# BadUSB-W.net
KiCad netlist of a schematic drawn in EAGLE
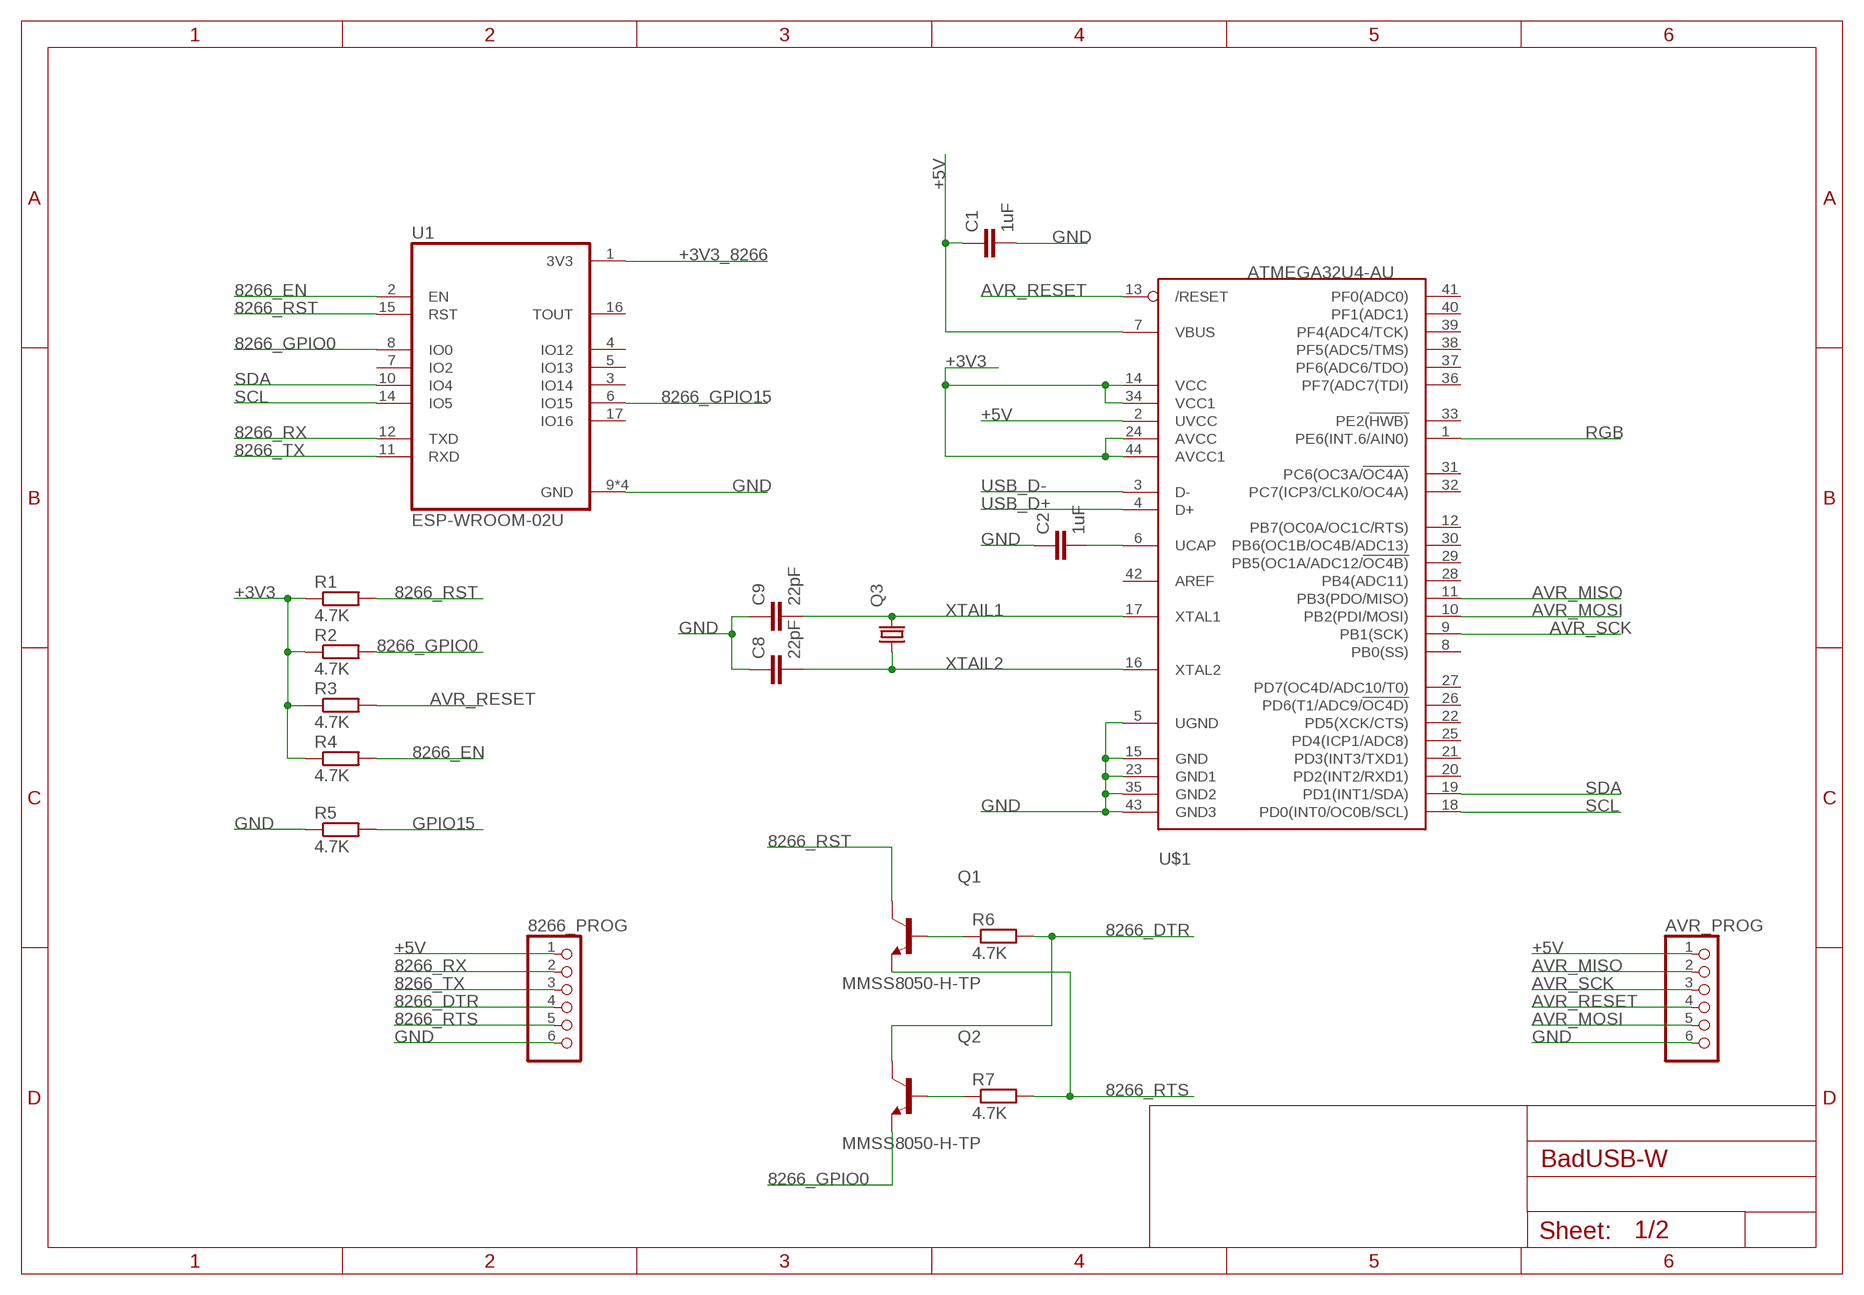
[diagram p0: schematic, sheet 1]
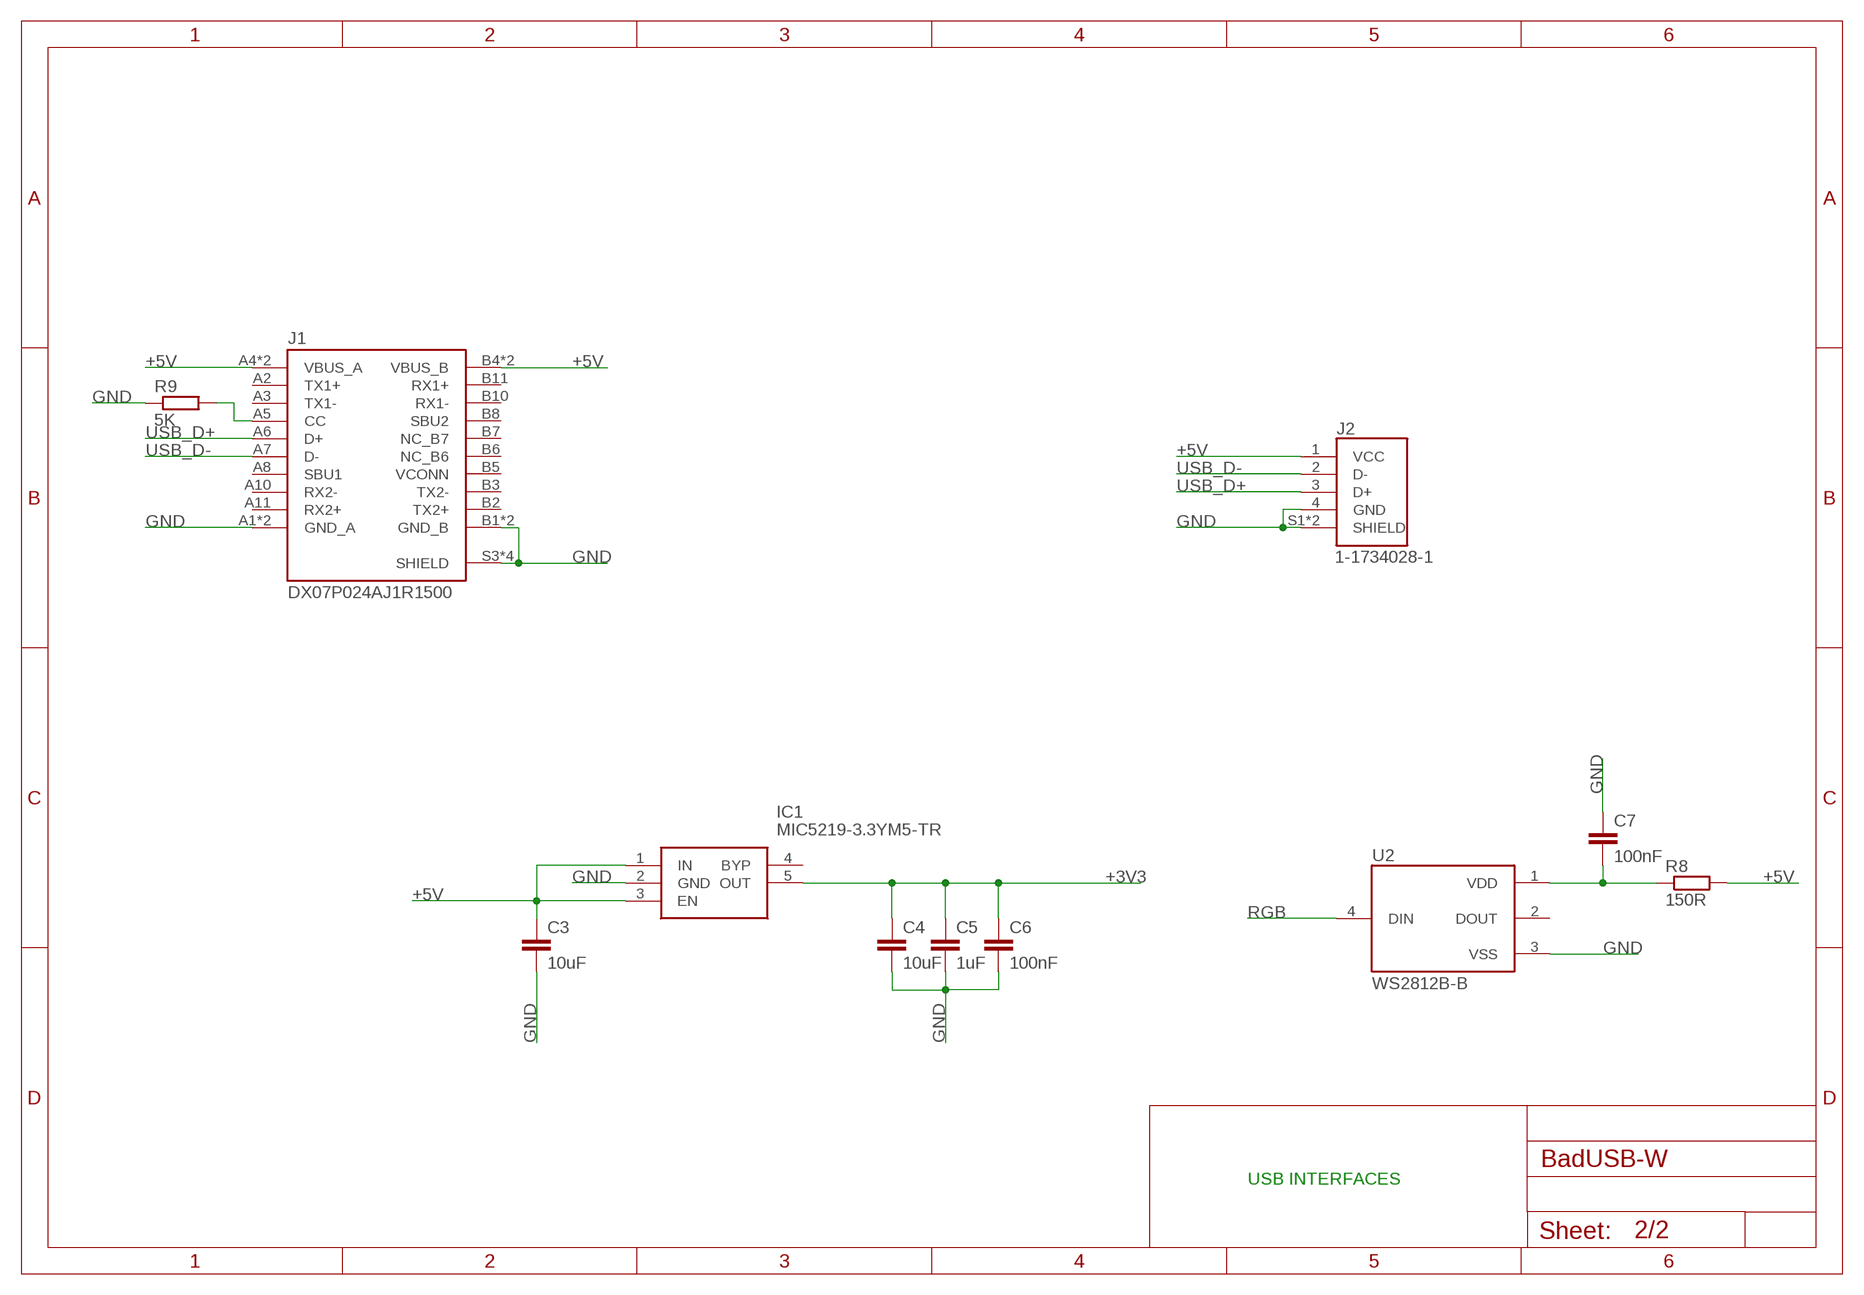
[diagram p1: schematic, sheet 2]

(export (version "E")
  (design (tool "Eeschema 10.0.6"))
  (components
    (comp (ref "C3")
      (value "10uF")
      (footprint "eagle-import:C0603K")
      (libsource (lib "eagle-import") (part "C-EUC0603K"))
    )
    (comp (ref "C4")
      (value "10uF")
      (footprint "eagle-import:C0603K")
      (libsource (lib "eagle-import") (part "C-EUC0603K"))
    )
    (comp (ref "C5")
      (value "1uF")
      (footprint "eagle-import:C0603K")
      (libsource (lib "eagle-import") (part "C-EUC0603K"))
    )
    (comp (ref "C6")
      (value "100nF")
      (footprint "eagle-import:C0603K")
      (libsource (lib "eagle-import") (part "C-EUC0603K"))
    )
    (comp (ref "C7")
      (value "100nF")
      (footprint "eagle-import:C0603K")
      (libsource (lib "eagle-import") (part "C-EUC0603K"))
    )
    (comp (ref "IC1")
      (value "MIC5219-3.3YM5-TR")
      (footprint "eagle-import:SOT95P280X130-5N")
      (fields (field (name "MOUSER_PART_NUMBER") "998-MIC5219-3.3YM5TR"))
      (libsource (lib "eagle-import") (part "MIC5219-3.3YM5-TR"))
    )
    (comp (ref "J1")
      (value "DX07P024AJ1R1500")
      (footprint "eagle-import:JAE_DX07P024AJ1R1500")
      (fields (field (name "MF") "JAE Electronics"))
      (libsource (lib "eagle-import") (part "DX07P024AJ1R1500"))
    )
    (comp (ref "J2")
      (value "1-1734028-1")
      (footprint "eagle-import:TE_1-1734028-1")
      (fields (field (name "MF") "TE Connectivity"))
      (libsource (lib "eagle-import") (part "1-1734028-1"))
    )
    (comp (ref "R8")
      (value "150R")
      (footprint "eagle-import:R0603")
      (libsource (lib "eagle-import") (part "R-EU_R0603"))
    )
    (comp (ref "R9")
      (value "5K")
      (footprint "eagle-import:R0603")
      (libsource (lib "eagle-import") (part "R-EU_R0603"))
    )
    (comp (ref "U2")
      (value "WS2812B-B")
      (footprint "eagle-import:LED_WS2812B-B")
      (fields (field (name "MF") "Worldsemi"))
      (libsource (lib "eagle-import") (part "WS2812B-B"))
    )
    (comp (ref "8266_PROG")
      (value "PINHD-1X6")
      (footprint "eagle-import:1X06")
      (libsource (lib "eagle-import") (part "PINHD-1X6"))
    )
    (comp (ref "AVR_PROG")
      (value "PINHD-1X6")
      (footprint "eagle-import:1X06")
      (libsource (lib "eagle-import") (part "PINHD-1X6"))
    )
    (comp (ref "C1")
      (value "1uF")
      (footprint "eagle-import:C0603K")
      (libsource (lib "eagle-import") (part "C-EUC0603K"))
    )
    (comp (ref "C2")
      (value "1uF")
      (footprint "eagle-import:C0603K")
      (libsource (lib "eagle-import") (part "C-EUC0603K"))
    )
    (comp (ref "C8")
      (value "22pF")
      (footprint "eagle-import:C0603K")
      (libsource (lib "eagle-import") (part "C-EUC0603K"))
    )
    (comp (ref "C9")
      (value "22pF")
      (footprint "eagle-import:C0603K")
      (libsource (lib "eagle-import") (part "C-EUC0603K"))
    )
    (comp (ref "Q1")
      (value "MMSS8050-H-TP")
      (footprint "eagle-import:TRANS_MMSS8050-H-TP")
      (fields (field (name "MF") "Micro Commercial"))
      (libsource (lib "eagle-import") (part "MMSS8050-H-TP"))
    )
    (comp (ref "Q2")
      (value "MMSS8050-H-TP")
      (footprint "eagle-import:TRANS_MMSS8050-H-TP")
      (fields (field (name "MF") "Micro Commercial"))
      (libsource (lib "eagle-import") (part "MMSS8050-H-TP"))
    )
    (comp (ref "Q3")
      (value "KX-7")
      (footprint "eagle-import:3.2X2.5_KX-7")
      (libsource (lib "eagle-import") (part "KX-7"))
    )
    (comp (ref "R1")
      (value "4.7K")
      (footprint "eagle-import:R0603")
      (libsource (lib "eagle-import") (part "R-EU_R0603"))
    )
    (comp (ref "R2")
      (value "4.7K")
      (footprint "eagle-import:R0603")
      (libsource (lib "eagle-import") (part "R-EU_R0603"))
    )
    (comp (ref "R3")
      (value "4.7K")
      (footprint "eagle-import:R0603")
      (libsource (lib "eagle-import") (part "R-EU_R0603"))
    )
    (comp (ref "R4")
      (value "4.7K")
      (footprint "eagle-import:R0603")
      (libsource (lib "eagle-import") (part "R-EU_R0603"))
    )
    (comp (ref "R5")
      (value "4.7K")
      (footprint "eagle-import:R0603")
      (libsource (lib "eagle-import") (part "R-EU_R0603"))
    )
    (comp (ref "R6")
      (value "4.7K")
      (footprint "eagle-import:R0603")
      (libsource (lib "eagle-import") (part "R-EU_R0603"))
    )
    (comp (ref "R7")
      (value "4.7K")
      (footprint "eagle-import:R0603")
      (libsource (lib "eagle-import") (part "R-EU_R0603"))
    )
    (comp (ref "U$1")
      (value "ATMEGA32U4-AU")
      (footprint "eagle-import:TQFP44")
      (libsource (lib "eagle-import") (part "ATMEGA32U4-AU"))
    )
    (comp (ref "U1")
      (value "ESP-WROOM-02U")
      (footprint "eagle-import:MODULE_ESP-WROOM-02U")
      (fields (field (name "MF") "Espressif Systems"))
      (libsource (lib "eagle-import") (part "ESP-WROOM-02U"))
    )
  )
  (nets
    (net (code "1") (name "+3V3") (class "Default")
      (node (ref "C4") (pin "1") (pinfunction "1_1") (pintype "passive"))
      (node (ref "C5") (pin "1") (pinfunction "1_1") (pintype "passive"))
      (node (ref "C6") (pin "1") (pinfunction "1_1") (pintype "passive"))
      (node (ref "IC1") (pin "5") (pinfunction "OUT_5") (pintype "bidirectional"))
      (node (ref "R1") (pin "1") (pinfunction "1_1") (pintype "passive"))
      (node (ref "R2") (pin "1") (pinfunction "1_1") (pintype "passive"))
      (node (ref "R3") (pin "1") (pinfunction "1_1") (pintype "passive"))
      (node (ref "R4") (pin "1") (pinfunction "1_1") (pintype "passive"))
      (node (ref "U$1") (pin "14") (pinfunction "VCC_14") (pintype "bidirectional"))
      (node (ref "U$1") (pin "24") (pinfunction "AVCC_24") (pintype "bidirectional"))
      (node (ref "U$1") (pin "34") (pinfunction "VCC1_34") (pintype "bidirectional"))
      (node (ref "U$1") (pin "44") (pinfunction "AVCC1_44") (pintype "bidirectional"))
    )
    (net (code "2") (name "+3V3_8266") (class "Default")
      (node (ref "U1") (pin "1") (pinfunction "3V3_1") (pintype "power_in"))
    )
    (net (code "3") (name "+5V") (class "Default")
      (node (ref "8266_PROG") (pin "1") (pinfunction "1_1") (pintype "passive"))
      (node (ref "AVR_PROG") (pin "1") (pinfunction "1_1") (pintype "passive"))
      (node (ref "C1") (pin "1") (pinfunction "1_1") (pintype "passive"))
      (node (ref "C3") (pin "1") (pinfunction "1_1") (pintype "passive"))
      (node (ref "IC1") (pin "1") (pinfunction "IN_1") (pintype "bidirectional"))
      (node (ref "IC1") (pin "3") (pinfunction "EN_3") (pintype "bidirectional"))
      (node (ref "J1") (pin "A4") (pinfunction "VBUS_A_A4") (pintype "power_in"))
      (node (ref "J1") (pin "A9") (pinfunction "VBUS_A_A9") (pintype "power_in"))
      (node (ref "J1") (pin "B4") (pinfunction "VBUS_B_B4") (pintype "power_in"))
      (node (ref "J1") (pin "B9") (pinfunction "VBUS_B_B9") (pintype "power_in"))
      (node (ref "J2") (pin "1") (pinfunction "VCC_1") (pintype "power_in"))
      (node (ref "R8") (pin "2") (pinfunction "2_2") (pintype "passive"))
      (node (ref "U$1") (pin "2") (pinfunction "UVCC_2") (pintype "bidirectional"))
      (node (ref "U$1") (pin "7") (pinfunction "VBUS_7") (pintype "bidirectional"))
    )
    (net (code "4") (name "8266_DTR") (class "Default")
      (node (ref "8266_PROG") (pin "4") (pinfunction "4_4") (pintype "passive"))
      (node (ref "Q2") (pin "3") (pinfunction "C_3") (pintype "passive"))
      (node (ref "R6") (pin "2") (pinfunction "2_2") (pintype "passive"))
    )
    (net (code "5") (name "8266_EN") (class "Default")
      (node (ref "R4") (pin "2") (pinfunction "2_2") (pintype "passive"))
      (node (ref "U1") (pin "2") (pinfunction "EN_2") (pintype "input"))
    )
    (net (code "6") (name "8266_GPIO0") (class "Default")
      (node (ref "Q2") (pin "2") (pinfunction "E_2") (pintype "passive"))
      (node (ref "R2") (pin "2") (pinfunction "2_2") (pintype "passive"))
      (node (ref "U1") (pin "8") (pinfunction "IO0_8") (pintype "bidirectional"))
    )
    (net (code "7") (name "8266_GPIO15") (class "Default")
      (node (ref "U1") (pin "6") (pinfunction "IO15_6") (pintype "bidirectional"))
    )
    (net (code "8") (name "8266_RST") (class "Default")
      (node (ref "Q1") (pin "3") (pinfunction "C_3") (pintype "passive"))
      (node (ref "R1") (pin "2") (pinfunction "2_2") (pintype "passive"))
      (node (ref "U1") (pin "15") (pinfunction "RST_15") (pintype "input"))
    )
    (net (code "9") (name "8266_RTS") (class "Default")
      (node (ref "8266_PROG") (pin "5") (pinfunction "5_5") (pintype "passive"))
      (node (ref "Q1") (pin "2") (pinfunction "E_2") (pintype "passive"))
      (node (ref "R7") (pin "2") (pinfunction "2_2") (pintype "passive"))
    )
    (net (code "10") (name "8266_RX") (class "Default")
      (node (ref "8266_PROG") (pin "2") (pinfunction "2_2") (pintype "passive"))
      (node (ref "U1") (pin "12") (pinfunction "TXD_12") (pintype "bidirectional"))
    )
    (net (code "11") (name "8266_TX") (class "Default")
      (node (ref "8266_PROG") (pin "3") (pinfunction "3_3") (pintype "passive"))
      (node (ref "U1") (pin "11") (pinfunction "RXD_11") (pintype "bidirectional"))
    )
    (net (code "12") (name "AVR_MISO") (class "Default")
      (node (ref "AVR_PROG") (pin "2") (pinfunction "2_2") (pintype "passive"))
      (node (ref "U$1") (pin "11") (pinfunction "PB3(PDO/MISO)_11") (pintype "bidirectional"))
    )
    (net (code "13") (name "AVR_MOSI") (class "Default")
      (node (ref "AVR_PROG") (pin "5") (pinfunction "5_5") (pintype "passive"))
      (node (ref "U$1") (pin "10") (pinfunction "PB2(PDI/MOSI)_10") (pintype "bidirectional"))
    )
    (net (code "14") (name "AVR_RESET") (class "Default")
      (node (ref "AVR_PROG") (pin "4") (pinfunction "4_4") (pintype "passive"))
      (node (ref "R3") (pin "2") (pinfunction "2_2") (pintype "passive"))
      (node (ref "U$1") (pin "13") (pinfunction "/RESET_13") (pintype "bidirectional"))
    )
    (net (code "15") (name "AVR_SCK") (class "Default")
      (node (ref "AVR_PROG") (pin "3") (pinfunction "3_3") (pintype "passive"))
      (node (ref "U$1") (pin "9") (pinfunction "PB1(SCK)_9") (pintype "bidirectional"))
    )
    (net (code "16") (name "GND") (class "Default")
      (node (ref "8266_PROG") (pin "6") (pinfunction "6_6") (pintype "passive"))
      (node (ref "AVR_PROG") (pin "6") (pinfunction "6_6") (pintype "passive"))
      (node (ref "C1") (pin "2") (pinfunction "2_2") (pintype "passive"))
      (node (ref "C2") (pin "1") (pinfunction "1_1") (pintype "passive"))
      (node (ref "C3") (pin "2") (pinfunction "2_2") (pintype "passive"))
      (node (ref "C4") (pin "2") (pinfunction "2_2") (pintype "passive"))
      (node (ref "C5") (pin "2") (pinfunction "2_2") (pintype "passive"))
      (node (ref "C6") (pin "2") (pinfunction "2_2") (pintype "passive"))
      (node (ref "C7") (pin "1") (pinfunction "1_1") (pintype "passive"))
      (node (ref "C8") (pin "1") (pinfunction "1_1") (pintype "passive"))
      (node (ref "C9") (pin "1") (pinfunction "1_1") (pintype "passive"))
      (node (ref "IC1") (pin "2") (pinfunction "GND_2") (pintype "bidirectional"))
      (node (ref "J1") (pin "A1") (pinfunction "GND_A_A1") (pintype "power_in"))
      (node (ref "J1") (pin "A12") (pinfunction "GND_A_A12") (pintype "power_in"))
      (node (ref "J1") (pin "B1") (pinfunction "GND_B_B1") (pintype "power_in"))
      (node (ref "J1") (pin "B12") (pinfunction "GND_B_B12") (pintype "power_in"))
      (node (ref "J1") (pin "S3") (pinfunction "SHIELD_S3") (pintype "passive"))
      (node (ref "J1") (pin "S4") (pinfunction "SHIELD_S4") (pintype "passive"))
      (node (ref "J1") (pin "S5") (pinfunction "SHIELD_S5") (pintype "passive"))
      (node (ref "J1") (pin "S6") (pinfunction "SHIELD_S6") (pintype "passive"))
      (node (ref "J2") (pin "4") (pinfunction "GND_4") (pintype "power_in"))
      (node (ref "J2") (pin "S1") (pinfunction "SHIELD_S1") (pintype "power_in"))
      (node (ref "J2") (pin "S2") (pinfunction "SHIELD_S2") (pintype "power_in"))
      (node (ref "R5") (pin "1") (pinfunction "1_1") (pintype "passive"))
      (node (ref "R9") (pin "1") (pinfunction "1_1") (pintype "passive"))
      (node (ref "U$1") (pin "15") (pinfunction "GND_15") (pintype "bidirectional"))
      (node (ref "U$1") (pin "23") (pinfunction "GND1_23") (pintype "bidirectional"))
      (node (ref "U$1") (pin "35") (pinfunction "GND2_35") (pintype "bidirectional"))
      (node (ref "U$1") (pin "43") (pinfunction "GND3_43") (pintype "bidirectional"))
      (node (ref "U$1") (pin "5") (pinfunction "UGND_5") (pintype "bidirectional"))
      (node (ref "U1") (pin "13") (pinfunction "GND_13") (pintype "power_in"))
      (node (ref "U1") (pin "18") (pinfunction "GND_18") (pintype "power_in"))
      (node (ref "U1") (pin "19") (pinfunction "GND_19") (pintype "power_in"))
      (node (ref "U1") (pin "9") (pinfunction "GND_9") (pintype "power_in"))
      (node (ref "U2") (pin "3") (pinfunction "VSS_3") (pintype "power_in"))
    )
    (net (code "17") (name "GPIO15") (class "Default")
      (node (ref "R5") (pin "2") (pinfunction "2_2") (pintype "passive"))
    )
    (net (code "18") (name "Net-(J1-CC)") (class "Default")
      (node (ref "J1") (pin "A5") (pinfunction "CC_A5") (pintype "bidirectional"))
      (node (ref "R9") (pin "2") (pinfunction "2_2") (pintype "passive"))
    )
    (net (code "19") (name "Net-(Q1-B)") (class "Default")
      (node (ref "Q1") (pin "1") (pinfunction "B_1") (pintype "passive"))
      (node (ref "R6") (pin "1") (pinfunction "1_1") (pintype "passive"))
    )
    (net (code "20") (name "Net-(Q2-B)") (class "Default")
      (node (ref "Q2") (pin "1") (pinfunction "B_1") (pintype "passive"))
      (node (ref "R7") (pin "1") (pinfunction "1_1") (pintype "passive"))
    )
    (net (code "21") (name "Net-(U$1-UCAP)") (class "Default")
      (node (ref "C2") (pin "2") (pinfunction "2_2") (pintype "passive"))
      (node (ref "U$1") (pin "6") (pinfunction "UCAP_6") (pintype "bidirectional"))
    )
    (net (code "22") (name "Net-(U2-VDD)") (class "Default")
      (node (ref "C7") (pin "2") (pinfunction "2_2") (pintype "passive"))
      (node (ref "R8") (pin "1") (pinfunction "1_1") (pintype "passive"))
      (node (ref "U2") (pin "1") (pinfunction "VDD_1") (pintype "power_in"))
    )
    (net (code "23") (name "RGB") (class "Default")
      (node (ref "U$1") (pin "1") (pinfunction "PE6(INT.6/AIN0)_1") (pintype "bidirectional"))
      (node (ref "U2") (pin "4") (pinfunction "DIN_4") (pintype "input"))
    )
    (net (code "24") (name "SCL") (class "Default")
      (node (ref "U$1") (pin "18") (pinfunction "PD0(INT0/OC0B/SCL)_18") (pintype "bidirectional"))
      (node (ref "U1") (pin "14") (pinfunction "IO5_14") (pintype "bidirectional"))
    )
    (net (code "25") (name "SDA") (class "Default")
      (node (ref "U$1") (pin "19") (pinfunction "PD1(INT1/SDA)_19") (pintype "bidirectional"))
      (node (ref "U1") (pin "10") (pinfunction "IO4_10") (pintype "bidirectional"))
    )
    (net (code "26") (name "USB_D+") (class "Default")
      (node (ref "J1") (pin "A6") (pinfunction "D+_A6") (pintype "bidirectional"))
      (node (ref "J2") (pin "3") (pinfunction "D+_3") (pintype "bidirectional"))
      (node (ref "U$1") (pin "4") (pinfunction "D+_4") (pintype "bidirectional"))
    )
    (net (code "27") (name "USB_D-") (class "Default")
      (node (ref "J1") (pin "A7") (pinfunction "D-_A7") (pintype "bidirectional"))
      (node (ref "J2") (pin "2") (pinfunction "D-_2") (pintype "bidirectional"))
      (node (ref "U$1") (pin "3") (pinfunction "D-_3") (pintype "bidirectional"))
    )
    (net (code "28") (name "XTAIL1") (class "Default")
      (node (ref "C9") (pin "2") (pinfunction "2_2") (pintype "passive"))
      (node (ref "Q3") (pin "3") (pinfunction "2_3") (pintype "passive"))
      (node (ref "U$1") (pin "17") (pinfunction "XTAL1_17") (pintype "bidirectional"))
    )
    (net (code "29") (name "XTAIL2") (class "Default")
      (node (ref "C8") (pin "2") (pinfunction "2_2") (pintype "passive"))
      (node (ref "Q3") (pin "1") (pinfunction "1_1") (pintype "passive"))
      (node (ref "U$1") (pin "16") (pinfunction "XTAL2_16") (pintype "bidirectional"))
    )
    (net (code "30") (name "unconnected-(IC1-BYP-Pad4)") (class "Default")
      (node (ref "IC1") (pin "4") (pinfunction "BYP_4") (pintype "bidirectional"))
    )
    (net (code "31") (name "unconnected-(J1-NC_B6-PadB6)") (class "Default")
      (node (ref "J1") (pin "B6") (pinfunction "NC_B6_B6") (pintype "no_connect"))
    )
    (net (code "32") (name "unconnected-(J1-NC_B7-PadB7)") (class "Default")
      (node (ref "J1") (pin "B7") (pinfunction "NC_B7_B7") (pintype "no_connect"))
    )
    (net (code "33") (name "unconnected-(J1-RX1+-PadB11)") (class "Default")
      (node (ref "J1") (pin "B11") (pinfunction "RX1+_B11") (pintype "bidirectional"))
    )
    (net (code "34") (name "unconnected-(J1-RX1--PadB10)") (class "Default")
      (node (ref "J1") (pin "B10") (pinfunction "RX1-_B10") (pintype "bidirectional"))
    )
    (net (code "35") (name "unconnected-(J1-RX2+-PadA11)") (class "Default")
      (node (ref "J1") (pin "A11") (pinfunction "RX2+_A11") (pintype "bidirectional"))
    )
    (net (code "36") (name "unconnected-(J1-RX2--PadA10)") (class "Default")
      (node (ref "J1") (pin "A10") (pinfunction "RX2-_A10") (pintype "bidirectional"))
    )
    (net (code "37") (name "unconnected-(J1-SBU1-PadA8)") (class "Default")
      (node (ref "J1") (pin "A8") (pinfunction "SBU1_A8") (pintype "bidirectional"))
    )
    (net (code "38") (name "unconnected-(J1-SBU2-PadB8)") (class "Default")
      (node (ref "J1") (pin "B8") (pinfunction "SBU2_B8") (pintype "bidirectional"))
    )
    (net (code "39") (name "unconnected-(J1-TX1+-PadA2)") (class "Default")
      (node (ref "J1") (pin "A2") (pinfunction "TX1+_A2") (pintype "bidirectional"))
    )
    (net (code "40") (name "unconnected-(J1-TX1--PadA3)") (class "Default")
      (node (ref "J1") (pin "A3") (pinfunction "TX1-_A3") (pintype "bidirectional"))
    )
    (net (code "41") (name "unconnected-(J1-TX2+-PadB2)") (class "Default")
      (node (ref "J1") (pin "B2") (pinfunction "TX2+_B2") (pintype "bidirectional"))
    )
    (net (code "42") (name "unconnected-(J1-TX2--PadB3)") (class "Default")
      (node (ref "J1") (pin "B3") (pinfunction "TX2-_B3") (pintype "bidirectional"))
    )
    (net (code "43") (name "unconnected-(J1-VCONN-PadB5)") (class "Default")
      (node (ref "J1") (pin "B5") (pinfunction "VCONN_B5") (pintype "bidirectional"))
    )
    (net (code "44") (name "unconnected-(U$1-AREF-Pad42)") (class "Default")
      (node (ref "U$1") (pin "42") (pinfunction "AREF_42") (pintype "bidirectional"))
    )
    (net (code "45") (name "unconnected-(U$1-PB0(SS)-Pad8)") (class "Default")
      (node (ref "U$1") (pin "8") (pinfunction "PB0(SS)_8") (pintype "bidirectional"))
    )
    (net (code "46") (name "unconnected-(U$1-PB4(ADC11)-Pad28)") (class "Default")
      (node (ref "U$1") (pin "28") (pinfunction "PB4(ADC11)_28") (pintype "bidirectional"))
    )
    (net (code "47") (name "unconnected-(U$1-PB5(OC1A{slash}ADC12{slash}~{OC4B})-Pad29)") (class "Default")
      (node (ref "U$1") (pin "29") (pinfunction "PB5(OC1A/ADC12/~{OC4B})_29") (pintype "bidirectional"))
    )
    (net (code "48") (name "unconnected-(U$1-PB6(OC1B{slash}OC4B{slash}ADC13)-Pad30)") (class "Default")
      (node (ref "U$1") (pin "30") (pinfunction "PB6(OC1B/OC4B/ADC13)_30") (pintype "bidirectional"))
    )
    (net (code "49") (name "unconnected-(U$1-PB7(OC0A{slash}OC1C{slash}RTS)-Pad12)") (class "Default")
      (node (ref "U$1") (pin "12") (pinfunction "PB7(OC0A/OC1C/RTS)_12") (pintype "bidirectional"))
    )
    (net (code "50") (name "unconnected-(U$1-PC6(OC3A{slash}~{OC4A})-Pad31)") (class "Default")
      (node (ref "U$1") (pin "31") (pinfunction "PC6(OC3A/~{OC4A})_31") (pintype "bidirectional"))
    )
    (net (code "51") (name "unconnected-(U$1-PC7(ICP3{slash}CLK0{slash}OC4A)-Pad32)") (class "Default")
      (node (ref "U$1") (pin "32") (pinfunction "PC7(ICP3/CLK0/OC4A)_32") (pintype "bidirectional"))
    )
    (net (code "52") (name "unconnected-(U$1-PD2(INT2{slash}RXD1)-Pad20)") (class "Default")
      (node (ref "U$1") (pin "20") (pinfunction "PD2(INT2/RXD1)_20") (pintype "bidirectional"))
    )
    (net (code "53") (name "unconnected-(U$1-PD3(INT3{slash}TXD1)-Pad21)") (class "Default")
      (node (ref "U$1") (pin "21") (pinfunction "PD3(INT3/TXD1)_21") (pintype "bidirectional"))
    )
    (net (code "54") (name "unconnected-(U$1-PD4(ICP1{slash}ADC8)-Pad25)") (class "Default")
      (node (ref "U$1") (pin "25") (pinfunction "PD4(ICP1/ADC8)_25") (pintype "bidirectional"))
    )
    (net (code "55") (name "unconnected-(U$1-PD5(XCK{slash}CTS)-Pad22)") (class "Default")
      (node (ref "U$1") (pin "22") (pinfunction "PD5(XCK/CTS)_22") (pintype "bidirectional"))
    )
    (net (code "56") (name "unconnected-(U$1-PD6(T1{slash}ADC9{slash}~{OC4D})-Pad26)") (class "Default")
      (node (ref "U$1") (pin "26") (pinfunction "PD6(T1/ADC9/~{OC4D})_26") (pintype "bidirectional"))
    )
    (net (code "57") (name "unconnected-(U$1-PD7(OC4D{slash}ADC10{slash}T0)-Pad27)") (class "Default")
      (node (ref "U$1") (pin "27") (pinfunction "PD7(OC4D/ADC10/T0)_27") (pintype "bidirectional"))
    )
    (net (code "58") (name "unconnected-(U$1-PE2(~{HWB})-Pad33)") (class "Default")
      (node (ref "U$1") (pin "33") (pinfunction "PE2(~{HWB})_33") (pintype "bidirectional"))
    )
    (net (code "59") (name "unconnected-(U$1-PF0(ADC0)-Pad41)") (class "Default")
      (node (ref "U$1") (pin "41") (pinfunction "PF0(ADC0)_41") (pintype "bidirectional"))
    )
    (net (code "60") (name "unconnected-(U$1-PF1(ADC1)-Pad40)") (class "Default")
      (node (ref "U$1") (pin "40") (pinfunction "PF1(ADC1)_40") (pintype "bidirectional"))
    )
    (net (code "61") (name "unconnected-(U$1-PF4(ADC4{slash}TCK)-Pad39)") (class "Default")
      (node (ref "U$1") (pin "39") (pinfunction "PF4(ADC4/TCK)_39") (pintype "bidirectional"))
    )
    (net (code "62") (name "unconnected-(U$1-PF5(ADC5{slash}TMS)-Pad38)") (class "Default")
      (node (ref "U$1") (pin "38") (pinfunction "PF5(ADC5/TMS)_38") (pintype "bidirectional"))
    )
    (net (code "63") (name "unconnected-(U$1-PF6(ADC6{slash}TDO)-Pad37)") (class "Default")
      (node (ref "U$1") (pin "37") (pinfunction "PF6(ADC6/TDO)_37") (pintype "bidirectional"))
    )
    (net (code "64") (name "unconnected-(U$1-PF7(ADC7(TDI)-Pad36)") (class "Default")
      (node (ref "U$1") (pin "36") (pinfunction "PF7(ADC7(TDI)_36") (pintype "bidirectional"))
    )
    (net (code "65") (name "unconnected-(U1-IO2-Pad7)") (class "Default")
      (node (ref "U1") (pin "7") (pinfunction "IO2_7") (pintype "bidirectional"))
    )
    (net (code "66") (name "unconnected-(U1-IO12-Pad4)") (class "Default")
      (node (ref "U1") (pin "4") (pinfunction "IO12_4") (pintype "bidirectional"))
    )
    (net (code "67") (name "unconnected-(U1-IO13-Pad5)") (class "Default")
      (node (ref "U1") (pin "5") (pinfunction "IO13_5") (pintype "bidirectional"))
    )
    (net (code "68") (name "unconnected-(U1-IO14-Pad3)") (class "Default")
      (node (ref "U1") (pin "3") (pinfunction "IO14_3") (pintype "bidirectional"))
    )
    (net (code "69") (name "unconnected-(U1-IO16-Pad17)") (class "Default")
      (node (ref "U1") (pin "17") (pinfunction "IO16_17") (pintype "bidirectional"))
    )
    (net (code "70") (name "unconnected-(U1-TOUT-Pad16)") (class "Default")
      (node (ref "U1") (pin "16") (pinfunction "TOUT_16") (pintype "bidirectional"))
    )
    (net (code "71") (name "unconnected-(U2-DOUT-Pad2)") (class "Default")
      (node (ref "U2") (pin "2") (pinfunction "DOUT_2") (pintype "output"))
    )
  )
)
